# 3_3VBuck_MP2225_P1.net
KiCad netlist of a schematic drawn in EasyEDA Pro
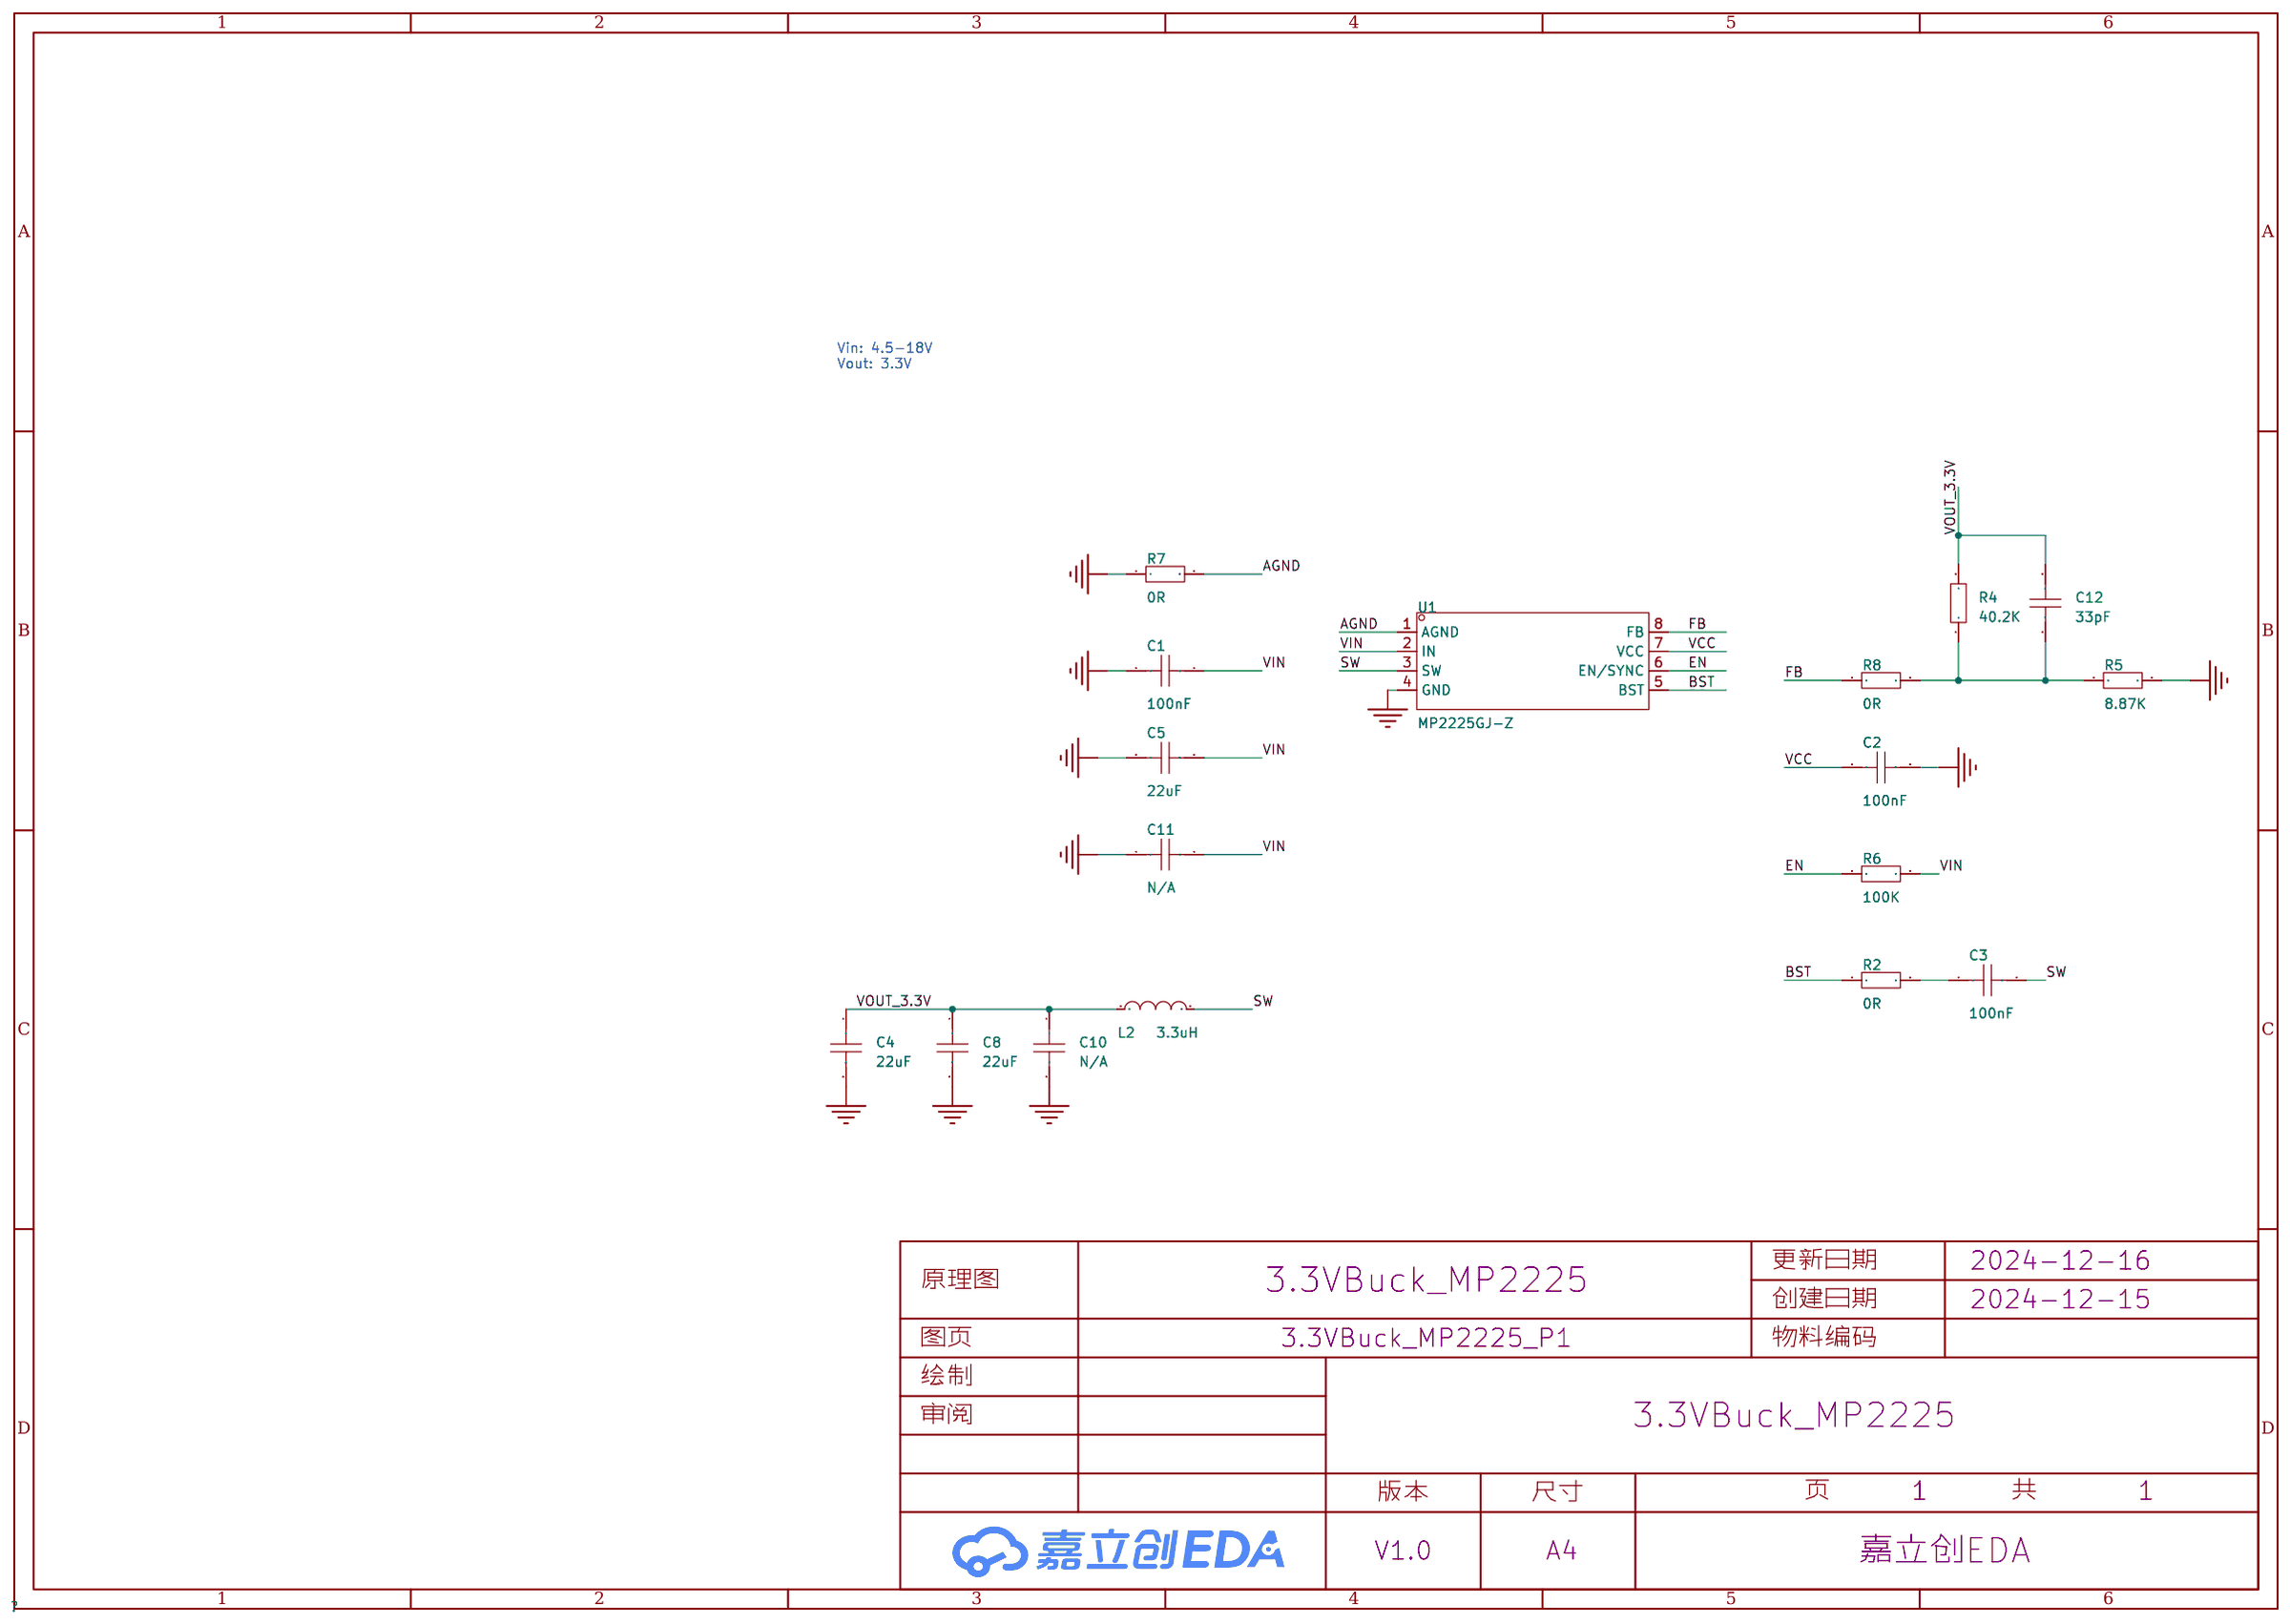
[diagram p0: schematic sheet]

(export (version "E")
  (design (tool "Eeschema 10.0.6"))
  (components
    (comp (ref "C1")
      (value "100nF")
      (footprint "easyedapro:C0805")
      (libsource (lib "easyedapro") (part "CapAcitance"))
    )
    (comp (ref "C2")
      (value "100nF")
      (footprint "easyedapro:C0805")
      (libsource (lib "easyedapro") (part "CapAcitance"))
    )
    (comp (ref "C3")
      (value "100nF")
      (footprint "easyedapro:C0805")
      (libsource (lib "easyedapro") (part "CapAcitance"))
    )
    (comp (ref "C4")
      (value "22uF")
      (footprint "easyedapro:C0805")
      (libsource (lib "easyedapro") (part "CapAcitance"))
    )
    (comp (ref "C5")
      (value "22uF")
      (footprint "easyedapro:C0805")
      (libsource (lib "easyedapro") (part "CapAcitance"))
    )
    (comp (ref "C8")
      (value "22uF")
      (footprint "easyedapro:C0805")
      (libsource (lib "easyedapro") (part "CapAcitance"))
    )
    (comp (ref "C10")
      (value "N/A")
      (footprint "easyedapro:C0805")
      (libsource (lib "easyedapro") (part "CapAcitance"))
    )
    (comp (ref "C11")
      (value "N/A")
      (footprint "easyedapro:C0805")
      (libsource (lib "easyedapro") (part "CapAcitance"))
    )
    (comp (ref "C12")
      (value "33pF")
      (footprint "easyedapro:C0805")
      (libsource (lib "easyedapro") (part "CapAcitance"))
    )
    (comp (ref "L2")
      (value "3.3uH")
      (footprint "easyedapro:IND-SMD_L7.1-W6.6_MJC-0603T")
      (description "电感值:5.6uH;精度:±20%;额定电流:5.5A;饱和电流(Isat):7A;类型:一体成型电感;")
      (fields
        (field (name "Manufacturer Part") "CXP0630-5R6M-AG(5.6uh)")
        (field (name "Manufacturer") "DMBJ(振宝佳)")
      )
      (libsource (lib "easyedapro") (part "CXP0630-5R6M-AG(5.6UH)"))
    )
    (comp (ref "R2") (value "0R") (footprint "easyedapro:R0805") (libsource (lib "easyedapro") (part "电阻")))
    (comp (ref "R4")
      (value "40.2K")
      (footprint "easyedapro:R0805")
      (libsource (lib "easyedapro") (part "电阻"))
    )
    (comp (ref "R5")
      (value "8.87K")
      (footprint "easyedapro:R0805")
      (libsource (lib "easyedapro") (part "电阻"))
    )
    (comp (ref "R6") (value "100K") (footprint "easyedapro:R0805") (libsource (lib "easyedapro") (part "电阻")))
    (comp (ref "R7") (value "0R") (footprint "easyedapro:R0805") (libsource (lib "easyedapro") (part "电阻")))
    (comp (ref "R8") (value "0R") (footprint "easyedapro:R0805") (libsource (lib "easyedapro") (part "电阻")))
    (comp (ref "U1")
      (value "MP2225GJ-Z")
      (footprint "easyedapro:TSOT-23-8_L2.9-W1.6-P0.65-LS2.8-BR")
      (description "功能类型:降压型;输出类型:可调;输入电压:4.5V~18V;输出电压:600mV~18V;输出电流:5A;")
      (fields (field (name "Manufacturer") "MPS(芯源)"))
      (libsource (lib "easyedapro") (part "MP2225GJ-Z"))
    )
  )
  (nets
    (net (code "1") (name "/AGND") (class "Default")
      (node (ref "R7") (pin "2") (pinfunction "2_2") (pintype "input"))
      (node (ref "U1") (pin "1") (pinfunction "AGND_1") (pintype "unspecified"))
    )
    (net (code "2") (name "/BST") (class "Default")
      (node (ref "R2") (pin "1") (pinfunction "1_1") (pintype "input"))
      (node (ref "U1") (pin "5") (pinfunction "BST_5") (pintype "unspecified"))
    )
    (net (code "3") (name "/EN") (class "Default")
      (node (ref "R6") (pin "2") (pinfunction "2_2") (pintype "input"))
      (node (ref "U1") (pin "6") (pinfunction "EN/SYNC_6") (pintype "unspecified"))
    )
    (net (code "4") (name "/FB") (class "Default")
      (node (ref "R8") (pin "1") (pinfunction "1_1") (pintype "input"))
      (node (ref "U1") (pin "8") (pinfunction "FB_8") (pintype "unspecified"))
    )
    (net (code "5") (name "/SW") (class "Default")
      (node (ref "C3") (pin "2") (pinfunction "2_2") (pintype "input"))
      (node (ref "L2") (pin "2") (pinfunction "2_2") (pintype "unspecified"))
      (node (ref "U1") (pin "3") (pinfunction "SW_3") (pintype "unspecified"))
    )
    (net (code "6") (name "/VCC") (class "Default")
      (node (ref "C2") (pin "1") (pinfunction "1_1") (pintype "input"))
      (node (ref "U1") (pin "7") (pinfunction "VCC_7") (pintype "unspecified"))
    )
    (net (code "7") (name "/VIN") (class "Default")
      (node (ref "C1") (pin "2") (pinfunction "2_2") (pintype "input"))
      (node (ref "C11") (pin "2") (pinfunction "2_2") (pintype "input"))
      (node (ref "C5") (pin "2") (pinfunction "2_2") (pintype "input"))
      (node (ref "R6") (pin "1") (pinfunction "1_1") (pintype "input"))
      (node (ref "U1") (pin "2") (pinfunction "IN_2") (pintype "unspecified"))
    )
    (net (code "8") (name "/VOUT_3.3V") (class "Default")
      (node (ref "C10") (pin "1") (pinfunction "1_1") (pintype "input"))
      (node (ref "C12") (pin "2") (pinfunction "2_2") (pintype "input"))
      (node (ref "C4") (pin "1") (pinfunction "1_1") (pintype "input"))
      (node (ref "C8") (pin "1") (pinfunction "1_1") (pintype "input"))
      (node (ref "L2") (pin "1") (pinfunction "1_1") (pintype "unspecified"))
      (node (ref "R4") (pin "2") (pinfunction "2_2") (pintype "input"))
    )
    (net (code "9") (name "GND") (class "Default")
      (node (ref "C1") (pin "1") (pinfunction "1_1") (pintype "input"))
      (node (ref "C10") (pin "2") (pinfunction "2_2") (pintype "input"))
      (node (ref "C11") (pin "1") (pinfunction "1_1") (pintype "input"))
      (node (ref "C2") (pin "2") (pinfunction "2_2") (pintype "input"))
      (node (ref "C4") (pin "2") (pinfunction "2_2") (pintype "input"))
      (node (ref "C5") (pin "1") (pinfunction "1_1") (pintype "input"))
      (node (ref "C8") (pin "2") (pinfunction "2_2") (pintype "input"))
      (node (ref "R5") (pin "2") (pinfunction "2_2") (pintype "input"))
      (node (ref "R7") (pin "1") (pinfunction "1_1") (pintype "input"))
      (node (ref "U1") (pin "4") (pinfunction "GND_4") (pintype "unspecified"))
    )
    (net (code "10") (name "Net-(C3-Pad1)") (class "Default")
      (node (ref "C3") (pin "1") (pinfunction "1_1") (pintype "input"))
      (node (ref "R2") (pin "2") (pinfunction "2_2") (pintype "input"))
    )
    (net (code "11") (name "Net-(C12-Pad1)") (class "Default")
      (node (ref "C12") (pin "1") (pinfunction "1_1") (pintype "input"))
      (node (ref "R4") (pin "1") (pinfunction "1_1") (pintype "input"))
      (node (ref "R5") (pin "1") (pinfunction "1_1") (pintype "input"))
      (node (ref "R8") (pin "2") (pinfunction "2_2") (pintype "input"))
    )
  )
)
